# spi_lcd_booster_dip_v3.net
KiCad netlist of a schematic drawn in EAGLE
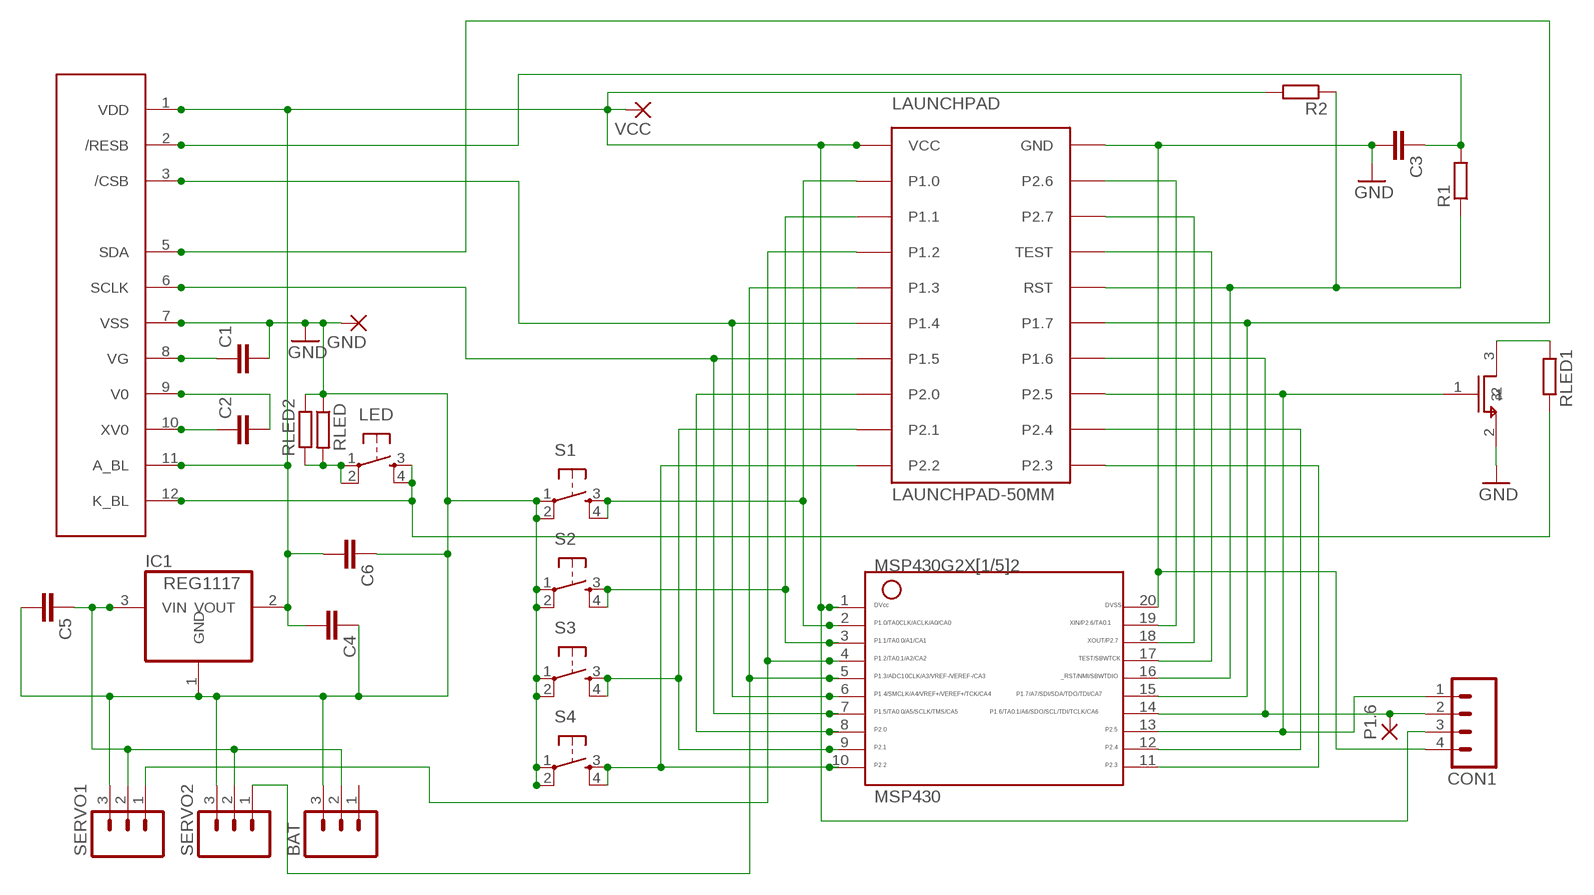
[diagram p0: schematic, sheet 1]

(export (version "E")
  (design (tool "Eeschema 10.0.6"))
  (components
    (comp (ref "BAT")
      (value "M03PTH")
      (footprint "eagle-import:1X03")
      (libsource (lib "eagle-import") (part "M03PTH"))
    )
    (comp (ref "C1")
      (value "CAP1206")
      (footprint "eagle-import:1206")
      (libsource (lib "eagle-import") (part "CAP1206"))
    )
    (comp (ref "C2")
      (value "CAP1206")
      (footprint "eagle-import:1206")
      (libsource (lib "eagle-import") (part "CAP1206"))
    )
    (comp (ref "C3")
      (value "CAP1206")
      (footprint "eagle-import:1206")
      (libsource (lib "eagle-import") (part "CAP1206"))
    )
    (comp (ref "C4")
      (value "CAP1206")
      (footprint "eagle-import:1206")
      (libsource (lib "eagle-import") (part "CAP1206"))
    )
    (comp (ref "C5")
      (value "CAP1206")
      (footprint "eagle-import:1206")
      (libsource (lib "eagle-import") (part "CAP1206"))
    )
    (comp (ref "C6")
      (value "CAP1206")
      (footprint "eagle-import:1206")
      (libsource (lib "eagle-import") (part "CAP1206"))
    )
    (comp (ref "CON1")
      (value "M04PTH")
      (footprint "eagle-import:1X04")
      (libsource (lib "eagle-import") (part "M04PTH"))
    )
    (comp (ref "GND")
      (value "2,15/1,0")
      (footprint "eagle-import:2,15_1,0")
      (libsource (lib "eagle-import") (part "2,15/1,0"))
    )
    (comp (ref "IC1")
      (value "REG1117")
      (footprint "eagle-import:SOT223")
      (libsource (lib "eagle-import") (part "REG1117"))
    )
    (comp (ref "LAUNCHPAD")
      (value "LAUNCHPAD-50MM")
      (footprint "eagle-import:LAUNCHPAD-50MM")
      (libsource (lib "eagle-import") (part "LAUNCHPAD-50MM"))
    )
    (comp (ref "LED")
      (value "TAC_SWITCHPTH")
      (footprint "eagle-import:TACTILE-PTH")
      (libsource (lib "eagle-import") (part "TAC_SWITCHPTH"))
    )
    (comp (ref "LEDSW")
      (value "2N7002PW")
      (footprint "eagle-import:SOT323-R")
      (libsource (lib "eagle-import") (part "2N7002PW"))
    )
    (comp (ref "MSP430")
      (value "G2X[1/5]2---N20")
      (footprint "eagle-import:N20")
      (libsource (lib "eagle-import") (part "G2X[1/5]2---N20"))
    )
    (comp (ref "P1.6")
      (value "2,15/1,0")
      (footprint "eagle-import:2,15_1,0")
      (libsource (lib "eagle-import") (part "2,15/1,0"))
    )
    (comp (ref "R1")
      (value "R-EU_R1206")
      (footprint "eagle-import:R1206")
      (libsource (lib "eagle-import") (part "R-EU_R1206"))
    )
    (comp (ref "R2")
      (value "R-EU_R1206")
      (footprint "eagle-import:R1206")
      (libsource (lib "eagle-import") (part "R-EU_R1206"))
    )
    (comp (ref "RLED")
      (value "R-EU_R1206")
      (footprint "eagle-import:R1206")
      (libsource (lib "eagle-import") (part "R-EU_R1206"))
    )
    (comp (ref "RLED1")
      (value "R-EU_R1206")
      (footprint "eagle-import:R1206")
      (libsource (lib "eagle-import") (part "R-EU_R1206"))
    )
    (comp (ref "RLED2")
      (value "R-EU_0207/10")
      (footprint "eagle-import:0207_10")
      (libsource (lib "eagle-import") (part "R-EU_0207/10"))
    )
    (comp (ref "S1")
      (value "TAC_SWITCHPTH")
      (footprint "eagle-import:TACTILE-PTH")
      (libsource (lib "eagle-import") (part "TAC_SWITCHPTH"))
    )
    (comp (ref "S2")
      (value "TAC_SWITCHPTH")
      (footprint "eagle-import:TACTILE-PTH")
      (libsource (lib "eagle-import") (part "TAC_SWITCHPTH"))
    )
    (comp (ref "S3")
      (value "TAC_SWITCHPTH")
      (footprint "eagle-import:TACTILE-PTH")
      (libsource (lib "eagle-import") (part "TAC_SWITCHPTH"))
    )
    (comp (ref "S4")
      (value "TAC_SWITCHPTH")
      (footprint "eagle-import:TACTILE-PTH")
      (libsource (lib "eagle-import") (part "TAC_SWITCHPTH"))
    )
    (comp (ref "SERVO1")
      (value "M03PTH")
      (footprint "eagle-import:1X03")
      (libsource (lib "eagle-import") (part "M03PTH"))
    )
    (comp (ref "SERVO2")
      (value "M03PTH")
      (footprint "eagle-import:1X03")
      (libsource (lib "eagle-import") (part "M03PTH"))
    )
    (comp (ref "U$1")
      (value "PE9665WRFPE9665WRF-WHOLE")
      (footprint "eagle-import:PE9665WRF")
      (libsource (lib "eagle-import") (part "PE9665WRFPE9665WRF-WHOLE"))
    )
    (comp (ref "VCC")
      (value "2,15/1,0")
      (footprint "eagle-import:2,15_1,0")
      (libsource (lib "eagle-import") (part "2,15/1,0"))
    )
  )
  (nets
    (net (code "1") (name "GND") (class "Default")
      (node (ref "BAT") (pin "3") (pinfunction "3_3") (pintype "passive"))
      (node (ref "C1") (pin "2") (pinfunction "2_2") (pintype "passive"))
      (node (ref "C3") (pin "2") (pinfunction "2_2") (pintype "passive"))
      (node (ref "C4") (pin "1") (pinfunction "1_1") (pintype "passive"))
      (node (ref "C5") (pin "2") (pinfunction "2_2") (pintype "passive"))
      (node (ref "C6") (pin "1") (pinfunction "1_1") (pintype "passive"))
      (node (ref "CON1") (pin "4") (pinfunction "4_4") (pintype "passive"))
      (node (ref "GND") (pin "1") (pinfunction "P_1") (pintype "passive"))
      (node (ref "IC1") (pin "1") (pinfunction "GND_1") (pintype "power_in"))
      (node (ref "LAUNCHPAD") (pin "GND") (pinfunction "GND_GND") (pintype "power_in"))
      (node (ref "LEDSW") (pin "2") (pinfunction "2_2") (pintype "bidirectional"))
      (node (ref "MSP430") (pin "20") (pinfunction "20_20") (pintype "bidirectional"))
      (node (ref "RLED") (pin "1") (pinfunction "1_1") (pintype "passive"))
      (node (ref "RLED2") (pin "2") (pinfunction "2_2") (pintype "passive"))
      (node (ref "S1") (pin "1") (pinfunction "1_1") (pintype "passive"))
      (node (ref "S1") (pin "2") (pinfunction "2_2") (pintype "passive"))
      (node (ref "S2") (pin "1") (pinfunction "1_1") (pintype "passive"))
      (node (ref "S2") (pin "2") (pinfunction "2_2") (pintype "passive"))
      (node (ref "S3") (pin "1") (pinfunction "1_1") (pintype "passive"))
      (node (ref "S3") (pin "2") (pinfunction "2_2") (pintype "passive"))
      (node (ref "S4") (pin "1") (pinfunction "1_1") (pintype "passive"))
      (node (ref "S4") (pin "2") (pinfunction "2_2") (pintype "passive"))
      (node (ref "SERVO1") (pin "3") (pinfunction "3_3") (pintype "passive"))
      (node (ref "SERVO2") (pin "3") (pinfunction "3_3") (pintype "passive"))
      (node (ref "U$1") (pin "7") (pinfunction "VSS_7") (pintype "bidirectional"))
    )
    (net (code "2") (name "Net-(CON1-Pad1)") (class "Default")
      (node (ref "CON1") (pin "1") (pinfunction "1_1") (pintype "passive"))
      (node (ref "LAUNCHPAD") (pin "P2.5") (pinfunction "P2.5_P2.5") (pintype "bidirectional"))
      (node (ref "LEDSW") (pin "1") (pinfunction "1_1") (pintype "bidirectional"))
      (node (ref "MSP430") (pin "13") (pinfunction "13_13") (pintype "bidirectional"))
    )
    (net (code "3") (name "Net-(IC1-VIN)") (class "Default")
      (node (ref "BAT") (pin "2") (pinfunction "2_2") (pintype "passive"))
      (node (ref "C5") (pin "1") (pinfunction "1_1") (pintype "passive"))
      (node (ref "IC1") (pin "3") (pinfunction "VIN_3") (pintype "input"))
      (node (ref "SERVO1") (pin "2") (pinfunction "2_2") (pintype "passive"))
      (node (ref "SERVO2") (pin "2") (pinfunction "2_2") (pintype "passive"))
    )
    (net (code "4") (name "Net-(IC1-VOUT)") (class "Default")
      (node (ref "C4") (pin "2") (pinfunction "2_2") (pintype "passive"))
      (node (ref "C6") (pin "2") (pinfunction "2_2") (pintype "passive"))
      (node (ref "CON1") (pin "3") (pinfunction "3_3") (pintype "passive"))
      (node (ref "IC1") (pin "2") (pinfunction "VOUT_2") (pintype "output"))
      (node (ref "LAUNCHPAD") (pin "VCC") (pinfunction "VCC_VCC") (pintype "power_in"))
      (node (ref "MSP430") (pin "1") (pinfunction "1_1") (pintype "bidirectional"))
      (node (ref "R2") (pin "2") (pinfunction "2_2") (pintype "passive"))
      (node (ref "U$1") (pin "1") (pinfunction "VDD_1") (pintype "bidirectional"))
      (node (ref "U$1") (pin "11") (pinfunction "A_BL_11") (pintype "bidirectional"))
      (node (ref "VCC") (pin "1") (pinfunction "P_1") (pintype "passive"))
    )
    (net (code "5") (name "Net-(LAUNCHPAD-PadP1.0)") (class "Default")
      (node (ref "LAUNCHPAD") (pin "P1.0") (pinfunction "P1.0_P1.0") (pintype "bidirectional"))
      (node (ref "MSP430") (pin "2") (pinfunction "2_2") (pintype "bidirectional"))
      (node (ref "S1") (pin "3") (pinfunction "3_3") (pintype "passive"))
      (node (ref "S1") (pin "4") (pinfunction "4_4") (pintype "passive"))
    )
    (net (code "6") (name "Net-(LAUNCHPAD-PadP1.1)") (class "Default")
      (node (ref "LAUNCHPAD") (pin "P1.1") (pinfunction "P1.1_P1.1") (pintype "bidirectional"))
      (node (ref "MSP430") (pin "3") (pinfunction "3_3") (pintype "bidirectional"))
      (node (ref "S2") (pin "3") (pinfunction "3_3") (pintype "passive"))
      (node (ref "S2") (pin "4") (pinfunction "4_4") (pintype "passive"))
    )
    (net (code "7") (name "Net-(LAUNCHPAD-PadP1.2)") (class "Default")
      (node (ref "LAUNCHPAD") (pin "P1.2") (pinfunction "P1.2_P1.2") (pintype "bidirectional"))
      (node (ref "MSP430") (pin "4") (pinfunction "4_4") (pintype "bidirectional"))
      (node (ref "SERVO1") (pin "1") (pinfunction "1_1") (pintype "passive"))
    )
    (net (code "8") (name "Net-(LAUNCHPAD-PadP1.3)") (class "Default")
      (node (ref "LAUNCHPAD") (pin "P1.3") (pinfunction "P1.3_P1.3") (pintype "bidirectional"))
      (node (ref "MSP430") (pin "5") (pinfunction "5_5") (pintype "bidirectional"))
      (node (ref "SERVO2") (pin "1") (pinfunction "1_1") (pintype "passive"))
    )
    (net (code "9") (name "Net-(LAUNCHPAD-PadP2.0)") (class "Default")
      (node (ref "LAUNCHPAD") (pin "P2.0") (pinfunction "P2.0_P2.0") (pintype "bidirectional"))
      (node (ref "MSP430") (pin "8") (pinfunction "8_8") (pintype "bidirectional"))
    )
    (net (code "10") (name "Net-(LAUNCHPAD-PadP2.1)") (class "Default")
      (node (ref "LAUNCHPAD") (pin "P2.1") (pinfunction "P2.1_P2.1") (pintype "bidirectional"))
      (node (ref "MSP430") (pin "9") (pinfunction "9_9") (pintype "bidirectional"))
      (node (ref "S3") (pin "3") (pinfunction "3_3") (pintype "passive"))
      (node (ref "S3") (pin "4") (pinfunction "4_4") (pintype "passive"))
    )
    (net (code "11") (name "Net-(LAUNCHPAD-PadP2.2)") (class "Default")
      (node (ref "LAUNCHPAD") (pin "P2.2") (pinfunction "P2.2_P2.2") (pintype "bidirectional"))
      (node (ref "MSP430") (pin "10") (pinfunction "10_10") (pintype "bidirectional"))
      (node (ref "S4") (pin "3") (pinfunction "3_3") (pintype "passive"))
      (node (ref "S4") (pin "4") (pinfunction "4_4") (pintype "passive"))
    )
    (net (code "12") (name "Net-(LAUNCHPAD-PadP2.3)") (class "Default")
      (node (ref "LAUNCHPAD") (pin "P2.3") (pinfunction "P2.3_P2.3") (pintype "bidirectional"))
      (node (ref "MSP430") (pin "11") (pinfunction "11_11") (pintype "bidirectional"))
    )
    (net (code "13") (name "Net-(LAUNCHPAD-PadP2.4)") (class "Default")
      (node (ref "LAUNCHPAD") (pin "P2.4") (pinfunction "P2.4_P2.4") (pintype "bidirectional"))
      (node (ref "MSP430") (pin "12") (pinfunction "12_12") (pintype "bidirectional"))
    )
    (net (code "14") (name "Net-(LAUNCHPAD-PadP2.6)") (class "Default")
      (node (ref "LAUNCHPAD") (pin "P2.6") (pinfunction "P2.6_P2.6") (pintype "bidirectional"))
      (node (ref "MSP430") (pin "19") (pinfunction "19_19") (pintype "bidirectional"))
    )
    (net (code "15") (name "Net-(LAUNCHPAD-PadP2.7)") (class "Default")
      (node (ref "LAUNCHPAD") (pin "P2.7") (pinfunction "P2.7_P2.7") (pintype "bidirectional"))
      (node (ref "MSP430") (pin "18") (pinfunction "18_18") (pintype "bidirectional"))
    )
    (net (code "16") (name "Net-(LAUNCHPAD-PadRST)") (class "Default")
      (node (ref "LAUNCHPAD") (pin "RST") (pinfunction "RST_RST") (pintype "bidirectional"))
      (node (ref "MSP430") (pin "16") (pinfunction "16_16") (pintype "bidirectional"))
      (node (ref "R1") (pin "1") (pinfunction "1_1") (pintype "passive"))
      (node (ref "R2") (pin "1") (pinfunction "1_1") (pintype "passive"))
    )
    (net (code "17") (name "Net-(LAUNCHPAD-PadTEST)") (class "Default")
      (node (ref "LAUNCHPAD") (pin "TEST") (pinfunction "TEST_TEST") (pintype "bidirectional"))
      (node (ref "MSP430") (pin "17") (pinfunction "17_17") (pintype "bidirectional"))
    )
    (net (code "18") (name "Net-(LED-Pad1)") (class "Default")
      (node (ref "LED") (pin "1") (pinfunction "1_1") (pintype "passive"))
      (node (ref "LED") (pin "2") (pinfunction "2_2") (pintype "passive"))
      (node (ref "RLED") (pin "2") (pinfunction "2_2") (pintype "passive"))
      (node (ref "RLED2") (pin "1") (pinfunction "1_1") (pintype "passive"))
    )
    (net (code "19") (name "Net-(LEDSW-Pad3)") (class "Default")
      (node (ref "LEDSW") (pin "3") (pinfunction "3_3") (pintype "bidirectional"))
      (node (ref "RLED1") (pin "1") (pinfunction "1_1") (pintype "passive"))
    )
    (net (code "20") (name "Net-(P1.6-P)") (class "Default")
      (node (ref "CON1") (pin "2") (pinfunction "2_2") (pintype "passive"))
      (node (ref "LAUNCHPAD") (pin "P1.6") (pinfunction "P1.6_P1.6") (pintype "bidirectional"))
      (node (ref "MSP430") (pin "14") (pinfunction "14_14") (pintype "bidirectional"))
      (node (ref "P1.6") (pin "1") (pinfunction "P_1") (pintype "passive"))
    )
    (net (code "21") (name "Net-(U$1-K_BL)") (class "Default")
      (node (ref "LED") (pin "3") (pinfunction "3_3") (pintype "passive"))
      (node (ref "LED") (pin "4") (pinfunction "4_4") (pintype "passive"))
      (node (ref "RLED1") (pin "2") (pinfunction "2_2") (pintype "passive"))
      (node (ref "U$1") (pin "12") (pinfunction "K_BL_12") (pintype "bidirectional"))
    )
    (net (code "22") (name "Net-(U$1-SCLK)") (class "Default")
      (node (ref "LAUNCHPAD") (pin "P1.5") (pinfunction "P1.5_P1.5") (pintype "bidirectional"))
      (node (ref "MSP430") (pin "7") (pinfunction "7_7") (pintype "bidirectional"))
      (node (ref "U$1") (pin "6") (pinfunction "SCLK_6") (pintype "bidirectional"))
    )
    (net (code "23") (name "Net-(U$1-SDA)") (class "Default")
      (node (ref "LAUNCHPAD") (pin "P1.7") (pinfunction "P1.7_P1.7") (pintype "bidirectional"))
      (node (ref "MSP430") (pin "15") (pinfunction "15_15") (pintype "bidirectional"))
      (node (ref "U$1") (pin "5") (pinfunction "SDA_5") (pintype "bidirectional"))
    )
    (net (code "24") (name "Net-(U$1-V0)") (class "Default")
      (node (ref "C2") (pin "2") (pinfunction "2_2") (pintype "passive"))
      (node (ref "U$1") (pin "9") (pinfunction "V0_9") (pintype "bidirectional"))
    )
    (net (code "25") (name "Net-(U$1-VG)") (class "Default")
      (node (ref "C1") (pin "1") (pinfunction "1_1") (pintype "passive"))
      (node (ref "U$1") (pin "8") (pinfunction "VG_8") (pintype "bidirectional"))
    )
    (net (code "26") (name "Net-(U$1-XV0)") (class "Default")
      (node (ref "C2") (pin "1") (pinfunction "1_1") (pintype "passive"))
      (node (ref "U$1") (pin "10") (pinfunction "XV0_10") (pintype "bidirectional"))
    )
    (net (code "27") (name "Net-(U$1-{slash}CSB)") (class "Default")
      (node (ref "LAUNCHPAD") (pin "P1.4") (pinfunction "P1.4_P1.4") (pintype "bidirectional"))
      (node (ref "MSP430") (pin "6") (pinfunction "6_6") (pintype "bidirectional"))
      (node (ref "U$1") (pin "3") (pinfunction "/CSB_3") (pintype "bidirectional"))
    )
    (net (code "28") (name "Net-(U$1-{slash}RESB)") (class "Default")
      (node (ref "C3") (pin "1") (pinfunction "1_1") (pintype "passive"))
      (node (ref "R1") (pin "2") (pinfunction "2_2") (pintype "passive"))
      (node (ref "U$1") (pin "2") (pinfunction "/RESB_2") (pintype "bidirectional"))
    )
    (net (code "29") (name "unconnected-(BAT-Pad1)") (class "Default")
      (node (ref "BAT") (pin "1") (pinfunction "1_1") (pintype "passive"))
    )
  )
)
